# lcd_duffle_pth_mk_7.net
KiCad netlist of a schematic drawn in EAGLE
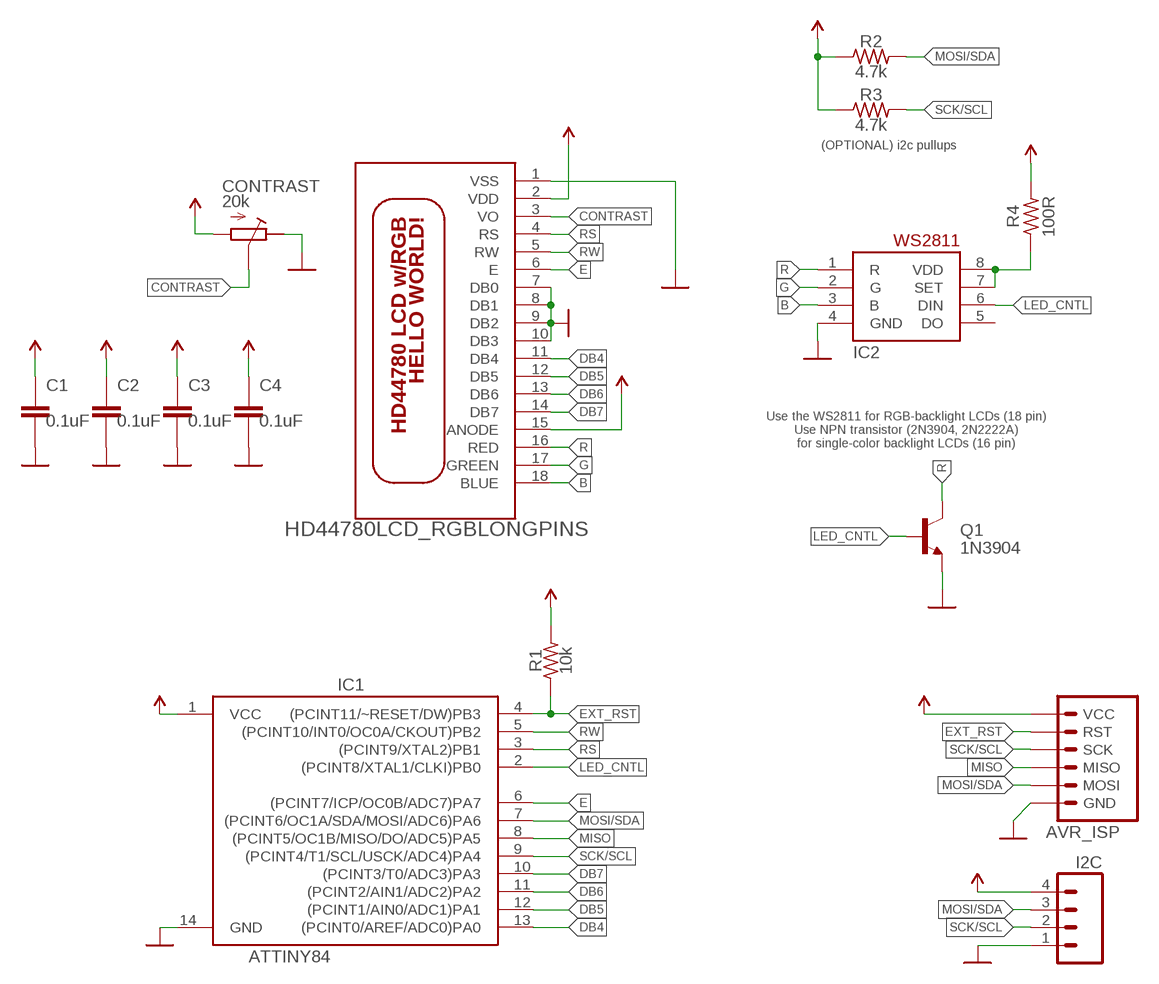
[diagram p0: schematic, sheet 1]

(export (version "E")
  (design (tool "Eeschema 10.0.6"))
  (components
    (comp (ref "AVR_ISP")
      (value "AVR_MINI_PROGJST-XH-RA-PTH")
      (footprint "eagle-import:AVR_MINI_PROG_JST_XH_RA")
      (libsource (lib "eagle-import") (part "AVR_MINI_PROGJST-XH-RA-PTH"))
    )
    (comp (ref "C1")
      (value "0.1uF")
      (footprint "eagle-import:C025-024X044")
      (libsource (lib "eagle-import") (part "CAPACITOR-CERAMIC025-024X044"))
    )
    (comp (ref "C2")
      (value "0.1uF")
      (footprint "eagle-import:C025-024X044")
      (libsource (lib "eagle-import") (part "CAPACITOR-CERAMIC025-024X044"))
    )
    (comp (ref "C3")
      (value "0.1uF")
      (footprint "eagle-import:C025-024X044")
      (libsource (lib "eagle-import") (part "CAPACITOR-CERAMIC025-024X044"))
    )
    (comp (ref "C4")
      (value "0.1uF")
      (footprint "eagle-import:C025-024X044")
      (libsource (lib "eagle-import") (part "CAPACITOR-CERAMIC025-024X044"))
    )
    (comp (ref "CONTRAST")
      (value "20k")
      (footprint "eagle-import:POT-THUMBWHEEL")
      (libsource (lib "eagle-import") (part "POTENTIOMETERTHUMBWHEEL-16MM"))
    )
    (comp (ref "I2C")
      (value "M04JST_XH_RA")
      (footprint "eagle-import:JST-4-XH-RA-PTH")
      (libsource (lib "eagle-import") (part "M04JST_XH_RA"))
    )
    (comp (ref "IC1")
      (value "ATTINY84")
      (footprint "eagle-import:DIL14")
      (libsource (lib "eagle-import") (part "ATTINY84ATTINY84-20PU"))
    )
    (comp (ref "IC2")
      (value "WS2811")
      (footprint "eagle-import:SO08-SKINNYPADS")
      (libsource (lib "eagle-import") (part "WS2811-SOP8"))
    )
    (comp (ref "Q1")
      (value "1N3904")
      (footprint "eagle-import:TO-92-AMMO")
      (libsource (lib "eagle-import") (part "TRANSISTOR_NPNTO-92-AMMO"))
    )
    (comp (ref "R1")
      (value "10k")
      (footprint "eagle-import:RESISTOR-AXIAL-PTH-5.08MM")
      (libsource (lib "eagle-import") (part "RESISTORPTH-AXIAL-5.08MM"))
    )
    (comp (ref "R2")
      (value "4.7k")
      (footprint "eagle-import:RESISTOR-AXIAL-PTH-5.08MM")
      (libsource (lib "eagle-import") (part "RESISTORPTH-AXIAL-5.08MM"))
    )
    (comp (ref "R3")
      (value "4.7k")
      (footprint "eagle-import:RESISTOR-AXIAL-PTH-5.08MM")
      (libsource (lib "eagle-import") (part "RESISTORPTH-AXIAL-5.08MM"))
    )
    (comp (ref "R4")
      (value "100R")
      (footprint "eagle-import:RESISTOR-AXIAL-PTH-5.08MM")
      (libsource (lib "eagle-import") (part "RESISTORPTH-AXIAL-5.08MM"))
    )
    (comp (ref "U$1")
      (value "HD44780LCD_RGBLONGPINS")
      (footprint "eagle-import:LCD1602-RGB-CENTERED")
      (libsource (lib "eagle-import") (part "HD44780LCD_RGBLONGPINS"))
    )
  )
  (nets
    (net (code "1") (name "5V") (class "Default")
      (node (ref "AVR_ISP") (pin "2") (pinfunction "VCC_2") (pintype "passive"))
      (node (ref "C1") (pin "2") (pinfunction "2_2") (pintype "passive"))
      (node (ref "C2") (pin "2") (pinfunction "2_2") (pintype "passive"))
      (node (ref "C3") (pin "2") (pinfunction "2_2") (pintype "passive"))
      (node (ref "C4") (pin "2") (pinfunction "2_2") (pintype "passive"))
      (node (ref "CONTRAST") (pin "1") (pinfunction "A_1") (pintype "passive"))
      (node (ref "I2C") (pin "4") (pinfunction "4_4") (pintype "passive"))
      (node (ref "IC1") (pin "1") (pinfunction "VCC_1") (pintype "bidirectional"))
      (node (ref "R1") (pin "P$2") (pinfunction "2_P$2") (pintype "passive"))
      (node (ref "R2") (pin "P$1") (pinfunction "1_P$1") (pintype "passive"))
      (node (ref "R3") (pin "P$1") (pinfunction "1_P$1") (pintype "passive"))
      (node (ref "R4") (pin "P$2") (pinfunction "2_P$2") (pintype "passive"))
      (node (ref "U$1") (pin "15") (pinfunction "ANODE_15") (pintype "input"))
      (node (ref "U$1") (pin "2") (pinfunction "VDD_2") (pintype "power_in"))
    )
    (net (code "2") (name "B") (class "Default")
      (node (ref "IC2") (pin "3") (pinfunction "B_3") (pintype "open_collector"))
      (node (ref "U$1") (pin "18") (pinfunction "BLUE_18") (pintype "input"))
    )
    (net (code "3") (name "CONTRAST") (class "Default")
      (node (ref "CONTRAST") (pin "2") (pinfunction "S_2") (pintype "passive"))
      (node (ref "CONTRAST") (pin "2@1") (pinfunction "S_2@1") (pintype "passive"))
      (node (ref "U$1") (pin "3") (pinfunction "VO_3") (pintype "input"))
    )
    (net (code "4") (name "DB4") (class "Default")
      (node (ref "IC1") (pin "13") (pinfunction "(PCINT0/AREF/ADC0)PA0_13") (pintype "bidirectional"))
      (node (ref "U$1") (pin "11") (pinfunction "DB4_11") (pintype "bidirectional"))
    )
    (net (code "5") (name "DB5") (class "Default")
      (node (ref "IC1") (pin "12") (pinfunction "(PCINT1/AIN0/ADC1)PA1_12") (pintype "bidirectional"))
      (node (ref "U$1") (pin "12") (pinfunction "DB5_12") (pintype "bidirectional"))
    )
    (net (code "6") (name "DB6") (class "Default")
      (node (ref "IC1") (pin "11") (pinfunction "(PCINT2/AIN1/ADC2)PA2_11") (pintype "bidirectional"))
      (node (ref "U$1") (pin "13") (pinfunction "DB6_13") (pintype "bidirectional"))
    )
    (net (code "7") (name "DB7") (class "Default")
      (node (ref "IC1") (pin "10") (pinfunction "(PCINT3/T0/ADC3)PA3_10") (pintype "bidirectional"))
      (node (ref "U$1") (pin "14") (pinfunction "DB7_14") (pintype "bidirectional"))
    )
    (net (code "8") (name "E") (class "Default")
      (node (ref "IC1") (pin "6") (pinfunction "(PCINT7/ICP/OC0B/ADC7)PA7_6") (pintype "bidirectional"))
      (node (ref "U$1") (pin "6") (pinfunction "E_6") (pintype "input"))
    )
    (net (code "9") (name "EXT_RST") (class "Default")
      (node (ref "AVR_ISP") (pin "5") (pinfunction "RST_5") (pintype "passive"))
      (node (ref "IC1") (pin "4") (pinfunction "(PCINT11/~{RESET/DW})PB3_4") (pintype "bidirectional"))
      (node (ref "R1") (pin "P$1") (pinfunction "1_P$1") (pintype "passive"))
    )
    (net (code "10") (name "G") (class "Default")
      (node (ref "IC2") (pin "2") (pinfunction "G_2") (pintype "open_collector"))
      (node (ref "U$1") (pin "17") (pinfunction "GREEN_17") (pintype "input"))
    )
    (net (code "11") (name "GND") (class "Default")
      (node (ref "AVR_ISP") (pin "6") (pinfunction "GND_6") (pintype "passive"))
      (node (ref "C1") (pin "1") (pinfunction "1_1") (pintype "passive"))
      (node (ref "C2") (pin "1") (pinfunction "1_1") (pintype "passive"))
      (node (ref "C3") (pin "1") (pinfunction "1_1") (pintype "passive"))
      (node (ref "C4") (pin "1") (pinfunction "1_1") (pintype "passive"))
      (node (ref "CONTRAST") (pin "3") (pinfunction "E_3") (pintype "passive"))
      (node (ref "I2C") (pin "1") (pinfunction "1_1") (pintype "passive"))
      (node (ref "IC1") (pin "14") (pinfunction "GND_14") (pintype "bidirectional"))
      (node (ref "IC2") (pin "4") (pinfunction "GND_4") (pintype "power_in"))
      (node (ref "Q1") (pin "1") (pinfunction "E_1") (pintype "passive"))
      (node (ref "U$1") (pin "1") (pinfunction "VSS_1") (pintype "power_in"))
      (node (ref "U$1") (pin "10") (pinfunction "DB3_10") (pintype "bidirectional"))
      (node (ref "U$1") (pin "7") (pinfunction "DB0_7") (pintype "bidirectional"))
      (node (ref "U$1") (pin "8") (pinfunction "DB1_8") (pintype "bidirectional"))
      (node (ref "U$1") (pin "9") (pinfunction "DB2_9") (pintype "bidirectional"))
    )
    (net (code "12") (name "LED_CNTL") (class "Default")
      (node (ref "IC1") (pin "2") (pinfunction "(PCINT8/XTAL1/CLKI)PB0_2") (pintype "bidirectional"))
      (node (ref "IC2") (pin "6") (pinfunction "DIN_6") (pintype "input"))
      (node (ref "Q1") (pin "2") (pinfunction "B_2") (pintype "passive"))
    )
    (net (code "13") (name "MISO") (class "Default")
      (node (ref "AVR_ISP") (pin "1") (pinfunction "MISO_1") (pintype "passive"))
      (node (ref "IC1") (pin "8") (pinfunction "(PCINT5/OC1B/MISO/DO/ADC5)PA5_8") (pintype "bidirectional"))
    )
    (net (code "14") (name "MOSI{slash}SDA") (class "Default")
      (node (ref "AVR_ISP") (pin "4") (pinfunction "MOSI_4") (pintype "passive"))
      (node (ref "I2C") (pin "3") (pinfunction "3_3") (pintype "passive"))
      (node (ref "IC1") (pin "7") (pinfunction "(PCINT6/OC1A/SDA/MOSI/ADC6)PA6_7") (pintype "bidirectional"))
      (node (ref "R2") (pin "P$2") (pinfunction "2_P$2") (pintype "passive"))
    )
    (net (code "15") (name "Net-(IC2-SET)") (class "Default")
      (node (ref "IC2") (pin "7") (pinfunction "SET_7") (pintype "input"))
      (node (ref "IC2") (pin "8") (pinfunction "VDD_8") (pintype "power_in"))
      (node (ref "R4") (pin "P$1") (pinfunction "1_P$1") (pintype "passive"))
    )
    (net (code "16") (name "R") (class "Default")
      (node (ref "IC2") (pin "1") (pinfunction "R_1") (pintype "open_collector"))
      (node (ref "Q1") (pin "3") (pinfunction "C_3") (pintype "passive"))
      (node (ref "U$1") (pin "16") (pinfunction "RED_16") (pintype "input"))
    )
    (net (code "17") (name "RS") (class "Default")
      (node (ref "IC1") (pin "3") (pinfunction "(PCINT9/XTAL2)PB1_3") (pintype "bidirectional"))
      (node (ref "U$1") (pin "4") (pinfunction "RS_4") (pintype "input"))
    )
    (net (code "18") (name "RW") (class "Default")
      (node (ref "IC1") (pin "5") (pinfunction "(PCINT10/INT0/OC0A/CKOUT)PB2_5") (pintype "bidirectional"))
      (node (ref "U$1") (pin "5") (pinfunction "RW_5") (pintype "input"))
    )
    (net (code "19") (name "SCK{slash}SCL") (class "Default")
      (node (ref "AVR_ISP") (pin "3") (pinfunction "SCK_3") (pintype "passive"))
      (node (ref "I2C") (pin "2") (pinfunction "2_2") (pintype "passive"))
      (node (ref "IC1") (pin "9") (pinfunction "(PCINT4/T1/SCL/USCK/ADC4)PA4_9") (pintype "bidirectional"))
      (node (ref "R3") (pin "P$2") (pinfunction "2_P$2") (pintype "passive"))
    )
    (net (code "20") (name "unconnected-(IC2-DO-Pad5)") (class "Default")
      (node (ref "IC2") (pin "5") (pinfunction "DO_5") (pintype "output"))
    )
  )
)
